# S7_Misc.net
KiCad netlist of a schematic drawn in Altium Designer
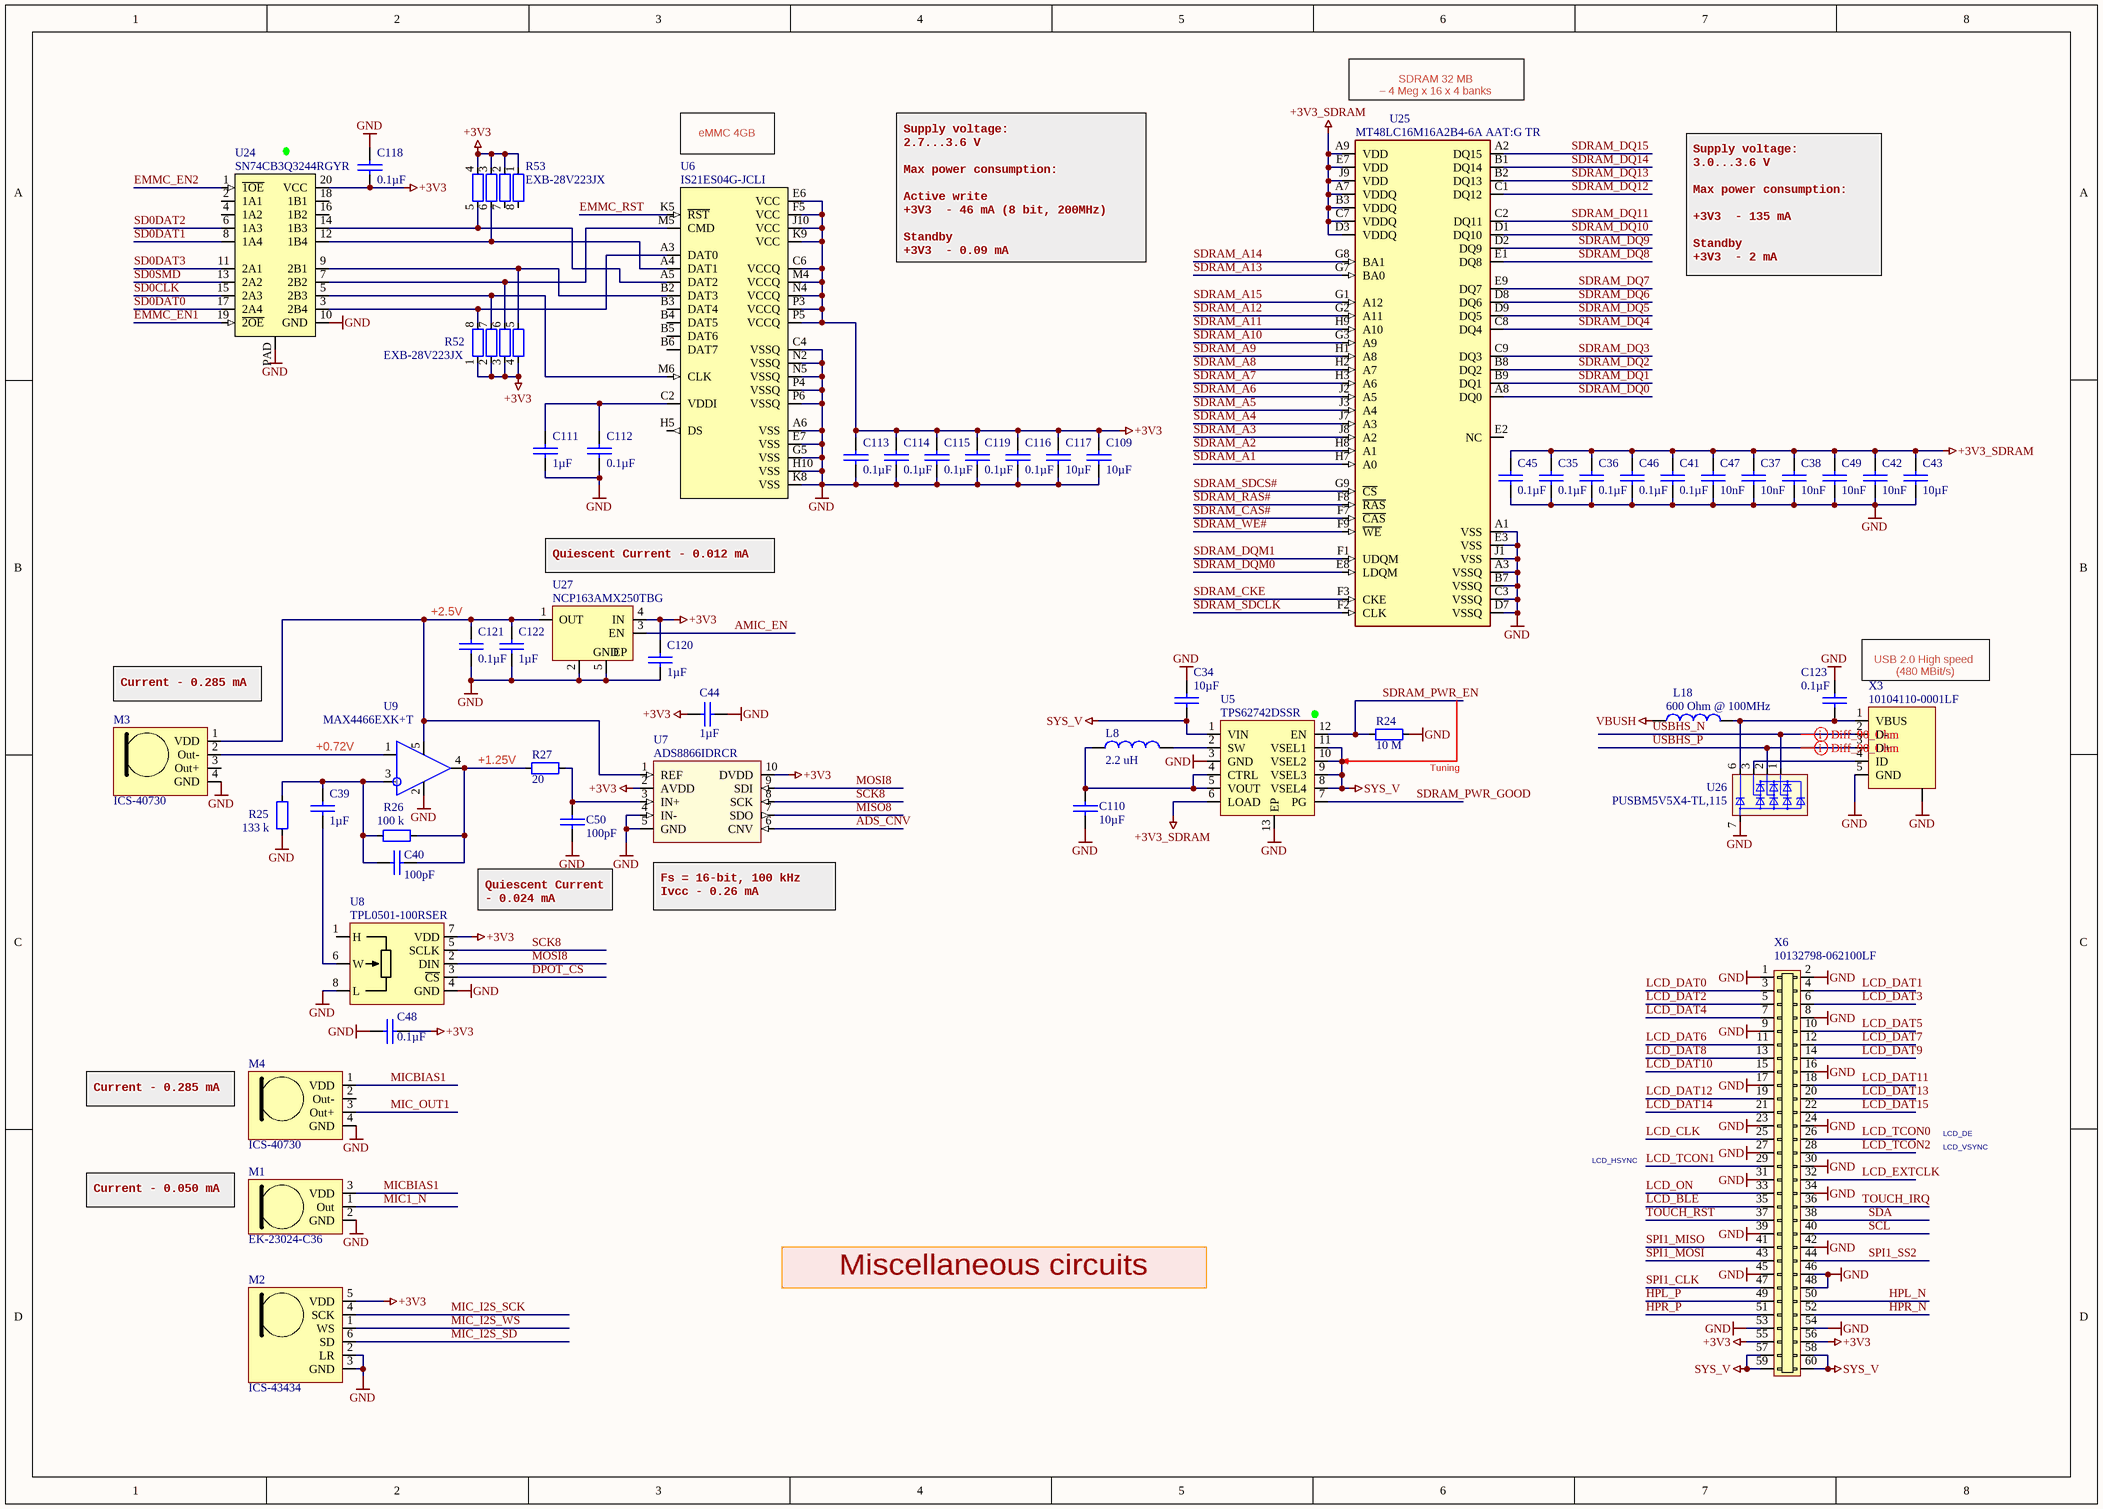
[diagram p0: S7_Misc.SchDoc]

(export (version "E")
  (design (tool "Eeschema 10.0.6"))
  (components
    (comp (ref "C34")
      (value "10µF")
      (footprint "0603 CAP")
      (description "10µF, ±10%, 16V, X5R, 0603 (1608 Metric), -55°C ~ 85°C, -, Automotive")
      (fields
        (field (name "PART NUMBER") "GRT188R61C106KE13D")
        (field (name "MANUFACTURER") "Murata Electronics North America")
      )
      (libsource (lib "ea_PassivComps") (part "Capacitor"))
    )
    (comp (ref "C35")
      (value "0.1µF")
      (footprint "0402 CAP")
      (description "0.1µF, ±10%, 50V, X7R, 0402 (1005 Metric), -55°C ~ 125°C, -, General Purpose")
      (fields
        (field (name "PART NUMBER") "0402B104K500CT")
        (field (name "MANUFACTURER") "Walsin Technology Corporation")
      )
      (libsource (lib "ea_PassivComps") (part "Capacitor"))
    )
    (comp (ref "C36")
      (value "0.1µF")
      (footprint "0402 CAP")
      (description "0.1µF, ±10%, 50V, X7R, 0402 (1005 Metric), -55°C ~ 125°C, -, General Purpose")
      (fields
        (field (name "PART NUMBER") "0402B104K500CT")
        (field (name "MANUFACTURER") "Walsin Technology Corporation")
      )
      (libsource (lib "ea_PassivComps") (part "Capacitor"))
    )
    (comp (ref "C37")
      (value "10nF")
      (footprint "0402 CAP")
      (description "10000pF, ±10%, 50V, X7R, 0402 (1005 Metric), -55°C ~ 125°C, -, General Purpose")
      (fields
        (field (name "PART NUMBER") "CL05B103KB5NNNC")
        (field (name "MANUFACTURER") "Samsung Electro-Mechanics")
      )
      (libsource (lib "ea_PassivComps") (part "Capacitor"))
    )
    (comp (ref "C38")
      (value "10nF")
      (footprint "0402 CAP")
      (description "10000pF, ±10%, 50V, X7R, 0402 (1005 Metric), -55°C ~ 125°C, -, General Purpose")
      (fields
        (field (name "PART NUMBER") "CL05B103KB5NNNC")
        (field (name "MANUFACTURER") "Samsung Electro-Mechanics")
      )
      (libsource (lib "ea_PassivComps") (part "Capacitor"))
    )
    (comp (ref "C39")
      (value "1µF")
      (footprint "0402 CAP")
      (description "1µF, ±20%, 25V, X5R, 0402 (1005 Metric), -55°C ~ 85°C, -, General Purpose")
      (fields (field (name "PART NUMBER") "TMK105BJ105MV-F") (field (name "MANUFACTURER") "Taiyo Yuden"))
      (libsource (lib "ea_PassivComps") (part "Capacitor"))
    )
    (comp (ref "C40")
      (value "100pF")
      (footprint "0402 CAP")
      (description "100pF, ±5%, 50V, C0G, NP0, 0402 (1005 Metric), -55°C ~ 125°C, -, Automotive")
      (fields (field (name "PART NUMBER") "AC0402JRNPO9BN101") (field (name "MANUFACTURER") "Yageo"))
      (libsource (lib "ea_PassivComps") (part "Capacitor"))
    )
    (comp (ref "C41")
      (value "0.1µF")
      (footprint "0402 CAP")
      (description "0.1µF, ±10%, 50V, X7R, 0402 (1005 Metric), -55°C ~ 125°C, -, General Purpose")
      (fields
        (field (name "PART NUMBER") "0402B104K500CT")
        (field (name "MANUFACTURER") "Walsin Technology Corporation")
      )
      (libsource (lib "ea_PassivComps") (part "Capacitor"))
    )
    (comp (ref "C42")
      (value "10nF")
      (footprint "0402 CAP")
      (description "10000pF, ±10%, 50V, X7R, 0402 (1005 Metric), -55°C ~ 125°C, -, General Purpose")
      (fields
        (field (name "PART NUMBER") "CL05B103KB5NNNC")
        (field (name "MANUFACTURER") "Samsung Electro-Mechanics")
      )
      (libsource (lib "ea_PassivComps") (part "Capacitor"))
    )
    (comp (ref "C43")
      (value "10µF")
      (footprint "0603 CAP")
      (description "10µF, ±10%, 16V, X5R, 0603 (1608 Metric), -55°C ~ 85°C, -, Automotive")
      (fields
        (field (name "PART NUMBER") "GRT188R61C106KE13D")
        (field (name "MANUFACTURER") "Murata Electronics North America")
      )
      (libsource (lib "ea_PassivComps") (part "Capacitor"))
    )
    (comp (ref "C44")
      (value "1µF")
      (footprint "0402 CAP")
      (description "1µF, ±20%, 25V, X5R, 0402 (1005 Metric), -55°C ~ 85°C, -, General Purpose")
      (fields (field (name "PART NUMBER") "TMK105BJ105MV-F") (field (name "MANUFACTURER") "Taiyo Yuden"))
      (libsource (lib "ea_PassivComps") (part "Capacitor"))
    )
    (comp (ref "C45")
      (value "0.1µF")
      (footprint "0402 CAP")
      (description "0.1µF, ±10%, 50V, X7R, 0402 (1005 Metric), -55°C ~ 125°C, -, General Purpose")
      (fields
        (field (name "PART NUMBER") "0402B104K500CT")
        (field (name "MANUFACTURER") "Walsin Technology Corporation")
      )
      (libsource (lib "ea_PassivComps") (part "Capacitor"))
    )
    (comp (ref "C46")
      (value "0.1µF")
      (footprint "0402 CAP")
      (description "0.1µF, ±10%, 50V, X7R, 0402 (1005 Metric), -55°C ~ 125°C, -, General Purpose")
      (fields
        (field (name "PART NUMBER") "0402B104K500CT")
        (field (name "MANUFACTURER") "Walsin Technology Corporation")
      )
      (libsource (lib "ea_PassivComps") (part "Capacitor"))
    )
    (comp (ref "C47")
      (value "10nF")
      (footprint "0402 CAP")
      (description "10000pF, ±10%, 50V, X7R, 0402 (1005 Metric), -55°C ~ 125°C, -, General Purpose")
      (fields
        (field (name "PART NUMBER") "CL05B103KB5NNNC")
        (field (name "MANUFACTURER") "Samsung Electro-Mechanics")
      )
      (libsource (lib "ea_PassivComps") (part "Capacitor"))
    )
    (comp (ref "C48")
      (value "0.1µF")
      (footprint "0402 CAP")
      (description "0.1µF, ±10%, 50V, X7R, 0402 (1005 Metric), -55°C ~ 125°C, -, General Purpose")
      (fields
        (field (name "PART NUMBER") "0402B104K500CT")
        (field (name "MANUFACTURER") "Walsin Technology Corporation")
      )
      (libsource (lib "ea_PassivComps") (part "Capacitor"))
    )
    (comp (ref "C49")
      (value "10nF")
      (footprint "0402 CAP")
      (description "10000pF, ±10%, 50V, X7R, 0402 (1005 Metric), -55°C ~ 125°C, -, General Purpose")
      (fields
        (field (name "PART NUMBER") "CL05B103KB5NNNC")
        (field (name "MANUFACTURER") "Samsung Electro-Mechanics")
      )
      (libsource (lib "ea_PassivComps") (part "Capacitor"))
    )
    (comp (ref "C50")
      (value "100pF")
      (footprint "0402 CAP")
      (description "100pF, ±5%, 50V, C0G, NP0, 0402 (1005 Metric), -55°C ~ 125°C, -, Automotive")
      (fields (field (name "PART NUMBER") "AC0402JRNPO9BN101") (field (name "MANUFACTURER") "Yageo"))
      (libsource (lib "ea_PassivComps") (part "Capacitor"))
    )
    (comp (ref "C109")
      (value "10µF")
      (footprint "0603 CAP")
      (description "10µF, ±10%, 16V, X5R, 0603 (1608 Metric), -55°C ~ 85°C, -, Automotive")
      (fields
        (field (name "PART NUMBER") "GRT188R61C106KE13D")
        (field (name "MANUFACTURER") "Murata Electronics North America")
      )
      (libsource (lib "ea_PassivComps") (part "Capacitor"))
    )
    (comp (ref "C110")
      (value "10µF")
      (footprint "0603 CAP")
      (description "10µF, ±10%, 16V, X5R, 0603 (1608 Metric), -55°C ~ 85°C, -, Automotive")
      (fields
        (field (name "PART NUMBER") "GRT188R61C106KE13D")
        (field (name "MANUFACTURER") "Murata Electronics North America")
      )
      (libsource (lib "ea_PassivComps") (part "Capacitor"))
    )
    (comp (ref "C111")
      (value "1µF")
      (footprint "0402 CAP")
      (description "1µF, ±20%, 25V, X5R, 0402 (1005 Metric), -55°C ~ 85°C, -, General Purpose")
      (fields (field (name "PART NUMBER") "TMK105BJ105MV-F") (field (name "MANUFACTURER") "Taiyo Yuden"))
      (libsource (lib "ea_PassivComps") (part "Capacitor"))
    )
    (comp (ref "C112")
      (value "0.1µF")
      (footprint "0402 CAP")
      (description "0.1µF, ±10%, 50V, X7R, 0402 (1005 Metric), -55°C ~ 125°C, -, General Purpose")
      (fields
        (field (name "PART NUMBER") "0402B104K500CT")
        (field (name "MANUFACTURER") "Walsin Technology Corporation")
      )
      (libsource (lib "ea_PassivComps") (part "Capacitor"))
    )
    (comp (ref "C113")
      (value "0.1µF")
      (footprint "0402 CAP")
      (description "0.1µF, ±10%, 50V, X7R, 0402 (1005 Metric), -55°C ~ 125°C, -, General Purpose")
      (fields
        (field (name "PART NUMBER") "0402B104K500CT")
        (field (name "MANUFACTURER") "Walsin Technology Corporation")
      )
      (libsource (lib "ea_PassivComps") (part "Capacitor"))
    )
    (comp (ref "C114")
      (value "0.1µF")
      (footprint "0402 CAP")
      (description "0.1µF, ±10%, 50V, X7R, 0402 (1005 Metric), -55°C ~ 125°C, -, General Purpose")
      (fields
        (field (name "PART NUMBER") "0402B104K500CT")
        (field (name "MANUFACTURER") "Walsin Technology Corporation")
      )
      (libsource (lib "ea_PassivComps") (part "Capacitor"))
    )
    (comp (ref "C115")
      (value "0.1µF")
      (footprint "0402 CAP")
      (description "0.1µF, ±10%, 50V, X7R, 0402 (1005 Metric), -55°C ~ 125°C, -, General Purpose")
      (fields
        (field (name "PART NUMBER") "0402B104K500CT")
        (field (name "MANUFACTURER") "Walsin Technology Corporation")
      )
      (libsource (lib "ea_PassivComps") (part "Capacitor"))
    )
    (comp (ref "C116")
      (value "0.1µF")
      (footprint "0402 CAP")
      (description "0.1µF, ±10%, 50V, X7R, 0402 (1005 Metric), -55°C ~ 125°C, -, General Purpose")
      (fields
        (field (name "PART NUMBER") "0402B104K500CT")
        (field (name "MANUFACTURER") "Walsin Technology Corporation")
      )
      (libsource (lib "ea_PassivComps") (part "Capacitor"))
    )
    (comp (ref "C117")
      (value "10µF")
      (footprint "0603 CAP")
      (description "10µF, ±10%, 16V, X5R, 0603 (1608 Metric), -55°C ~ 85°C, -, Automotive")
      (fields
        (field (name "PART NUMBER") "GRT188R61C106KE13D")
        (field (name "MANUFACTURER") "Murata Electronics North America")
      )
      (libsource (lib "ea_PassivComps") (part "Capacitor"))
    )
    (comp (ref "C118")
      (value "0.1µF")
      (footprint "0402 CAP")
      (description "0.1µF, ±10%, 50V, X7R, 0402 (1005 Metric), -55°C ~ 125°C, -, General Purpose")
      (fields
        (field (name "PART NUMBER") "0402B104K500CT")
        (field (name "MANUFACTURER") "Walsin Technology Corporation")
      )
      (libsource (lib "ea_PassivComps") (part "Capacitor"))
    )
    (comp (ref "C119")
      (value "0.1µF")
      (footprint "0402 CAP")
      (description "0.1µF, ±10%, 50V, X7R, 0402 (1005 Metric), -55°C ~ 125°C, -, General Purpose")
      (fields
        (field (name "PART NUMBER") "0402B104K500CT")
        (field (name "MANUFACTURER") "Walsin Technology Corporation")
      )
      (libsource (lib "ea_PassivComps") (part "Capacitor"))
    )
    (comp (ref "C120")
      (value "1µF")
      (footprint "0402 CAP")
      (description "1µF, ±20%, 25V, X5R, 0402 (1005 Metric), -55°C ~ 85°C, -, General Purpose")
      (fields (field (name "PART NUMBER") "TMK105BJ105MV-F") (field (name "MANUFACTURER") "Taiyo Yuden"))
      (libsource (lib "ea_PassivComps") (part "Capacitor"))
    )
    (comp (ref "C121")
      (value "0.1µF")
      (footprint "0402 CAP")
      (description "0.1µF, ±10%, 50V, X7R, 0402 (1005 Metric), -55°C ~ 125°C, -, General Purpose")
      (fields
        (field (name "PART NUMBER") "0402B104K500CT")
        (field (name "MANUFACTURER") "Walsin Technology Corporation")
      )
      (libsource (lib "ea_PassivComps") (part "Capacitor"))
    )
    (comp (ref "C122")
      (value "1µF")
      (footprint "0402 CAP")
      (description "1µF, ±20%, 25V, X5R, 0402 (1005 Metric), -55°C ~ 85°C, -, General Purpose")
      (fields (field (name "PART NUMBER") "TMK105BJ105MV-F") (field (name "MANUFACTURER") "Taiyo Yuden"))
      (libsource (lib "ea_PassivComps") (part "Capacitor"))
    )
    (comp (ref "C123")
      (value "0.1µF")
      (footprint "0402 CAP")
      (description "0.1µF, ±10%, 50V, X7R, 0402 (1005 Metric), -55°C ~ 125°C, -, General Purpose")
      (fields
        (field (name "PART NUMBER") "0402B104K500CT")
        (field (name "MANUFACTURER") "Walsin Technology Corporation")
      )
      (libsource (lib "ea_PassivComps") (part "Capacitor"))
    )
    (comp (ref "L8")
      (value "2.2 uH")
      (footprint "744025002")
      (description "Inductors 2.2 uH, 1.8 A, 0.066 Ohms, ±20% -40°C ~ 125°C, 2.8 x 2.8 mm")
      (fields (field (name "MANUFACTURER") "Wurth Electronics Inc") (field (name "PARTNUM") "732-2613-1-ND"))
      (libsource (lib "ea_Inductors") (part "744025002"))
    )
    (comp (ref "L18")
      (value "600 Ohm @ 100MHz")
      (footprint "0805")
      (description "FERRITE BEAD 600 OHM, 0805, -55°C ~ 125°C")
      (fields (field (name "MANUFACTURER") "TDK Corporation") (field (name "PARTNUM") "445-2206-1-ND"))
      (libsource (lib "ea_Inductors") (part "MPZ2012S601AT000"))
    )
    (comp (ref "M1")
      (value "EK-23024-C36")
      (footprint "EK-23024-C36")
      (fields (field (name "MANUFACTURER") "Knowles") (field (name "PARTNUM") "423-1121-ND"))
      (libsource (lib "ea_Sound_devices") (part "EK-23024-C36"))
    )
    (comp (ref "M2")
      (value "ICS-43434")
      (footprint "ICS-43434")
      (fields (field (name "MANUFACTURER") "TDK InvenSense") (field (name "PARTNUM") "1428-1066-1-ND"))
      (libsource (lib "ea_Sound_devices") (part "ICS-43434"))
    )
    (comp (ref "M3")
      (value "ICS-40730")
      (footprint "ICS-40730")
      (fields (field (name "MANUFACTURER") "TDK InvenSense") (field (name "PARTNUM") "1428-1141-1-ND"))
      (libsource (lib "ea_Sound_devices") (part "ICS-40730"))
    )
    (comp (ref "M4")
      (value "ICS-40730")
      (footprint "ICS-40730")
      (fields (field (name "MANUFACTURER") "TDK InvenSense") (field (name "PARTNUM") "1428-1141-1-ND"))
      (libsource (lib "ea_Sound_devices") (part "ICS-40730"))
    )
    (comp (ref "R24")
      (value "10 M")
      (footprint "0402")
      (description "10 MOhms, ±1%, 0.063W, 1/16W, Thick Film, ±100ppm/°C, 0402 (1005 Metric), -55°C ~ 155°C, -")
      (fields (field (name "MANUFACTURER") "Vishay Dale") (field (name "TOLERANCE") "±1%"))
      (libsource (lib "") (part "Resistor_1"))
    )
    (comp (ref "R25")
      (value "133 k")
      (footprint "0402")
      (fields
        (field (name "MANUFACTURER") "Stackpole Electronics Inc")
        (field (name "TOLERANCE") "±1%")
        (field (name "VOLTAGE") "75V")
      )
      (libsource (lib "ea_PassivComps") (part "Resistor"))
    )
    (comp (ref "R26")
      (value "100 k")
      (footprint "0402")
      (fields
        (field (name "MANUFACTURER") "Stackpole Electronics Inc")
        (field (name "TOLERANCE") "±1%")
        (field (name "VOLTAGE") "75V")
      )
      (libsource (lib "") (part "Resistor_1"))
    )
    (comp (ref "R27")
      (value "20")
      (footprint "0402")
      (fields
        (field (name "MANUFACTURER") "Stackpole Electronics Inc")
        (field (name "TOLERANCE") "±1%")
        (field (name "VOLTAGE") "75V")
      )
      (libsource (lib "") (part "Resistor_1"))
    )
    (comp (ref "R52")
      (value "EXB-28V223JX")
      (footprint "EXB28V 2x1 mm")
      (description "22k Ohm ±5%,  4 Resistor, -55°C ~ 125°C,(2.00mm x 1.00mm)")
      (fields (field (name "MANUFACTURER") "Panasonic Electronic Components") (field (name "TOLERANCE") "5%"))
      (libsource (lib "") (part "EXB-28V223JX_1"))
    )
    (comp (ref "R53")
      (value "EXB-28V223JX")
      (footprint "EXB28V 2x1 mm")
      (description "22k Ohm ±5%,  4 Resistor, -55°C ~ 125°C,(2.00mm x 1.00mm)")
      (fields (field (name "MANUFACTURER") "Panasonic Electronic Components") (field (name "TOLERANCE") "5%"))
      (libsource (lib "ea_Resistors") (part "EXB-28V223JX"))
    )
    (comp (ref "U5")
      (value "TPS62742DSSR")
      (footprint "12-WSON")
      (description "DCDC 1.8-3.3V, 400mA , Iq=360nA, -40°C ~ 85°C, 12-WSON (3x2)")
      (fields (field (name "MANUFACTURER") "Texas Instruments") (field (name "PARTNUM") "296-40852-1-ND"))
      (libsource (lib "ea_IC_Power_Reg_Ref_Sw") (part "TPS62742DSSR"))
    )
    (comp (ref "U6")
      (value "IS21ES04G-JCLI")
      (footprint "MICRON_WFBGA153")
      (description "4GByte eMMC, 200MHz, 2.7V ~ 3.6V, 153-VFBGA (11.5x13),  -40°C ~ 85°C")
      (fields
        (field (name "MANUFACTURER") "Integrated Silicon Solution Inc")
        (field (name "DISPLAY NAME") "IS21ES04G-JCLI")
      )
      (libsource (lib "ea_IC_NOR_NAND_FLASH") (part "IS21ES04G-JCLI"))
    )
    (comp (ref "U7")
      (value "ADS8866IDRCR")
      (footprint "TI S-PVSON-N10")
      (description "16-bit ADC, 100k, Pseudo-Differential, Single Ended, 2.7..3.6V,  -40°C...85°C, 10-VSON")
      (fields (field (name "MANUFACTURER") "Texas Instruments") (field (name "PARTNUM") "296-39886-1-ND"))
      (libsource (lib "ea_IC_ADC") (part "ADS8866IDRCR"))
    )
    (comp (ref "U8")
      (value "TPL0501-100RSER")
      (footprint "UQFN-8")
      (description "Digital Potentiometer 100k Ohm 1 Circuit 256 Taps SPI Interface, -40°C ~ 125°C,  8-UQFN (1.5x1.5)")
      (fields (field (name "MANUFACTURER") "Texas Instruments") (field (name "PARTNUM") "296-29585-1-ND"))
      (libsource (lib "ea_IC_Digital_Potentiometers") (part "TPL0501-100RSER"))
    )
    (comp (ref "U9")
      (value "MAX4466EXK+T")
      (footprint "SOT-353 ON Semi")
      (description "OpAmp, Class AB,  2.4V ~ 5.5V, -40°C ~ 85°C, SC-70-5")
      (fields (field (name "MANUFACTURER") "Maxim Integrated") (field (name "PARTNUM") "MAX4466EXK+CT-ND"))
      (libsource (lib "ea_IC_OPAmps_AnComparators") (part "MAX4466EXK+T"))
    )
    (comp (ref "U24")
      (value "SN74CB3Q3244RGYR")
      (footprint "TI_PVQFN-N20")
      (description "Bus Switch 4 x 1:1, 2.3V ~ 3.6V,  -40°C ~ 85°C, 20-VQFN (3.5x4.5)")
      (fields (field (name "MANUFACTURER") "Texas Instruments") (field (name "PARTNUM") "296-19127-1-ND"))
      (libsource (lib "ea_IC_registers_buffers") (part "SN74CB3Q3244RGYR"))
    )
    (comp (ref "U25")
      (value "MT48LC16M16A2B4-6A AAT:G TR")
      (footprint "MICRON_VFBGA54")
      (description "Micron SDRAM 256M-Bit 16Mx16, 3.3V, 167MHz, 5.4ns, -40°C ~ 105°C, 54-VFBGA (8x8)")
      (fields (field (name "MANUFACTURER") "Micron Technology Inc.") (field (name "PARTNUM") "557-1932-1-ND"))
      (libsource (lib "ea_IC_RAM") (part "MT48LC16M16A2B4-6A AAT{colon}G TR"))
    )
    (comp (ref "U26")
      (value "PUSBM5V5X4-TL,115")
      (footprint "DFN1616-6")
      (description "TVS DIODE 5.5VWM 12VC 6HXSON")
      (fields (field (name "MANUFACTURER") "NXP Semiconductors") (field (name "PARTNUM") "568-10921-1-ND"))
      (libsource (lib "ea_TVS_protection") (part "PUSBM5V5X4-TL,115"))
    )
    (comp (ref "U27")
      (value "NCP163AMX250TBG")
      (footprint "4-XDFN")
      (description "LDO 2.5V, 250 mA, Vin < 5.5V, Iq < 20uA, -40..+125 C,  4-XDFN (1x1)")
      (fields
        (field (name "MANUFACTURER") "ON Semiconductor")
        (field (name "PARTNUM") "NCP163AMX250TBGOSCT-ND")
      )
      (libsource (lib "ea_IC_Power_Reg_Ref_Sw") (part "NCP163AMX250TBG"))
    )
    (comp (ref "X3")
      (value "10104110-0001LF")
      (footprint "FCI micro USB B receptacle SMD")
      (description "USB - micro B USB 2.0 Receptacle Connector 5 Position Surface Mount, Right Angle")
      (fields (field (name "MANUFACTURER") "Amphenol FCI") (field (name "PARTNUM") "609-4052-1-ND"))
      (libsource (lib "ea_Connectors_USB") (part "10104110-0001LF"))
    )
    (comp (ref "X6")
      (value "10132798-062100LF")
      (footprint "10132798-062100LF")
      (fields (field (name "MANUFACTURER") "Amphenol ICC (FCI)") (field (name "PARTNUM") "609-5230-1-ND"))
      (libsource (lib "ea_Connectors_0.5_mm_pitch") (part "10132798-062100LF"))
    )
  )
  (nets
    (net (code "1") (name "+3V3") (class "Default")
      (node (ref "C109") (pin "1") (pinfunction "1_1") (pintype "passive"))
      (node (ref "C113") (pin "1") (pinfunction "1_1") (pintype "passive"))
      (node (ref "C114") (pin "1") (pinfunction "1_1") (pintype "passive"))
      (node (ref "C115") (pin "1") (pinfunction "1_1") (pintype "passive"))
      (node (ref "C116") (pin "1") (pinfunction "1_1") (pintype "passive"))
      (node (ref "C117") (pin "1") (pinfunction "1_1") (pintype "passive"))
      (node (ref "C118") (pin "2") (pinfunction "2_2") (pintype "passive"))
      (node (ref "C119") (pin "1") (pinfunction "1_1") (pintype "passive"))
      (node (ref "C120") (pin "1") (pinfunction "1_1") (pintype "passive"))
      (node (ref "C44") (pin "1") (pinfunction "1_1") (pintype "passive"))
      (node (ref "C48") (pin "2") (pinfunction "2_2") (pintype "passive"))
      (node (ref "M2") (pin "5") (pinfunction "VDD_5") (pintype "passive"))
      (node (ref "R52") (pin "1") (pinfunction "1_1") (pintype "passive"))
      (node (ref "R52") (pin "2") (pinfunction "2_2") (pintype "passive"))
      (node (ref "R52") (pin "3") (pinfunction "3_3") (pintype "passive"))
      (node (ref "R52") (pin "4") (pinfunction "4_4") (pintype "passive"))
      (node (ref "R53") (pin "1") (pinfunction "1_1") (pintype "passive"))
      (node (ref "R53") (pin "2") (pinfunction "2_2") (pintype "passive"))
      (node (ref "R53") (pin "3") (pinfunction "3_3") (pintype "passive"))
      (node (ref "R53") (pin "4") (pinfunction "4_4") (pintype "passive"))
      (node (ref "U24") (pin "20") (pinfunction "VCC_20") (pintype "power_in"))
      (node (ref "U27") (pin "4") (pinfunction "IN_4") (pintype "power_in"))
      (node (ref "U6") (pin "C6") (pinfunction "VCCQ_C6") (pintype "power_in"))
      (node (ref "U6") (pin "E6") (pinfunction "VCC_E6") (pintype "power_in"))
      (node (ref "U6") (pin "F5") (pinfunction "VCC_F5") (pintype "power_in"))
      (node (ref "U6") (pin "J10") (pinfunction "VCC_J10") (pintype "power_in"))
      (node (ref "U6") (pin "K9") (pinfunction "VCC_K9") (pintype "power_in"))
      (node (ref "U6") (pin "M4") (pinfunction "VCCQ_M4") (pintype "power_in"))
      (node (ref "U6") (pin "N4") (pinfunction "VCCQ_N4") (pintype "power_in"))
      (node (ref "U6") (pin "P3") (pinfunction "VCCQ_P3") (pintype "power_in"))
      (node (ref "U6") (pin "P5") (pinfunction "VCCQ_P5") (pintype "power_in"))
      (node (ref "U7") (pin "10") (pinfunction "DVDD_10") (pintype "power_in"))
      (node (ref "U7") (pin "2") (pinfunction "AVDD_2") (pintype "power_in"))
      (node (ref "U8") (pin "7") (pinfunction "VDD_7") (pintype "passive"))
      (node (ref "X6") (pin "55") (pinfunction "28_55") (pintype "passive"))
      (node (ref "X6") (pin "56") (pinfunction "29_56") (pintype "passive"))
    )
    (net (code "2") (name "+3V3_SDRAM") (class "Default")
      (node (ref "C35") (pin "1") (pinfunction "1_1") (pintype "passive"))
      (node (ref "C36") (pin "1") (pinfunction "1_1") (pintype "passive"))
      (node (ref "C37") (pin "1") (pinfunction "1_1") (pintype "passive"))
      (node (ref "C38") (pin "1") (pinfunction "1_1") (pintype "passive"))
      (node (ref "C41") (pin "1") (pinfunction "1_1") (pintype "passive"))
      (node (ref "C42") (pin "1") (pinfunction "1_1") (pintype "passive"))
      (node (ref "C43") (pin "1") (pinfunction "1_1") (pintype "passive"))
      (node (ref "C45") (pin "1") (pinfunction "1_1") (pintype "passive"))
      (node (ref "C46") (pin "1") (pinfunction "1_1") (pintype "passive"))
      (node (ref "C47") (pin "1") (pinfunction "1_1") (pintype "passive"))
      (node (ref "C49") (pin "1") (pinfunction "1_1") (pintype "passive"))
      (node (ref "U25") (pin "A7") (pinfunction "VDDQ_A7") (pintype "power_in"))
      (node (ref "U25") (pin "A9") (pinfunction "VDD_A9") (pintype "power_in"))
      (node (ref "U25") (pin "B3") (pinfunction "VDDQ_B3") (pintype "power_in"))
      (node (ref "U25") (pin "C7") (pinfunction "VDDQ_C7") (pintype "power_in"))
      (node (ref "U25") (pin "D3") (pinfunction "VDDQ_D3") (pintype "power_in"))
      (node (ref "U25") (pin "E7") (pinfunction "VDD_E7") (pintype "power_in"))
      (node (ref "U25") (pin "J9") (pinfunction "VDD_J9") (pintype "power_in"))
      (node (ref "U5") (pin "6") (pinfunction "LOAD_6") (pintype "passive"))
    )
    (net (code "3") (name "/ADS_CNV") (class "Default")
      (node (ref "U7") (pin "6") (pinfunction "CNV_6") (pintype "input"))
    )
    (net (code "4") (name "/AMIC_EN") (class "Default")
      (node (ref "U27") (pin "3") (pinfunction "EN_3") (pintype "power_in"))
    )
    (net (code "5") (name "/DPOT_CS") (class "Default")
      (node (ref "U8") (pin "3") (pinfunction "~{CS}_3") (pintype "passive"))
    )
    (net (code "6") (name "/EMMC_EN1") (class "Default")
      (node (ref "U24") (pin "19") (pinfunction "~{2OE}_19") (pintype "input"))
    )
    (net (code "7") (name "/EMMC_EN2") (class "Default")
      (node (ref "U24") (pin "1") (pinfunction "~{1OE}_1") (pintype "input"))
    )
    (net (code "8") (name "/EMMC_RST") (class "Default")
      (node (ref "U6") (pin "K5") (pinfunction "~{RST}_K5") (pintype "input"))
    )
    (net (code "9") (name "/HPL_N") (class "Default")
      (node (ref "X6") (pin "50") (pinfunction "26_50") (pintype "passive"))
    )
    (net (code "10") (name "/HPL_P") (class "Default")
      (node (ref "X6") (pin "49") (pinfunction "25_49") (pintype "passive"))
    )
    (net (code "11") (name "/HPR_N") (class "Default")
      (node (ref "X6") (pin "52") (pinfunction "27_52") (pintype "passive"))
    )
    (net (code "12") (name "/HPR_P") (class "Default")
      (node (ref "X6") (pin "51") (pinfunction "26_51") (pintype "passive"))
    )
    (net (code "13") (name "/LCD_BLE") (class "Default")
      (node (ref "X6") (pin "35") (pinfunction "18_35") (pintype "passive"))
    )
    (net (code "14") (name "/LCD_CLK") (class "Default")
      (node (ref "X6") (pin "25") (pinfunction "13_25") (pintype "passive"))
    )
    (net (code "15") (name "/LCD_DAT0") (class "Default")
      (node (ref "X6") (pin "3") (pinfunction "2_3") (pintype "passive"))
    )
    (net (code "16") (name "/LCD_DAT1") (class "Default")
      (node (ref "X6") (pin "4") (pinfunction "3_4") (pintype "passive"))
    )
    (net (code "17") (name "/LCD_DAT2") (class "Default")
      (node (ref "X6") (pin "5") (pinfunction "3_5") (pintype "passive"))
    )
    (net (code "18") (name "/LCD_DAT3") (class "Default")
      (node (ref "X6") (pin "6") (pinfunction "4_6") (pintype "passive"))
    )
    (net (code "19") (name "/LCD_DAT4") (class "Default")
      (node (ref "X6") (pin "7") (pinfunction "4_7") (pintype "passive"))
    )
    (net (code "20") (name "/LCD_DAT5") (class "Default")
      (node (ref "X6") (pin "10") (pinfunction "6_10") (pintype "passive"))
    )
    (net (code "21") (name "/LCD_DAT6") (class "Default")
      (node (ref "X6") (pin "11") (pinfunction "6_11") (pintype "passive"))
    )
    (net (code "22") (name "/LCD_DAT7") (class "Default")
      (node (ref "X6") (pin "12") (pinfunction "7_12") (pintype "passive"))
    )
    (net (code "23") (name "/LCD_DAT8") (class "Default")
      (node (ref "X6") (pin "13") (pinfunction "7_13") (pintype "passive"))
    )
    (net (code "24") (name "/LCD_DAT9") (class "Default")
      (node (ref "X6") (pin "14") (pinfunction "8_14") (pintype "passive"))
    )
    (net (code "25") (name "/LCD_DAT10") (class "Default")
      (node (ref "X6") (pin "15") (pinfunction "8_15") (pintype "passive"))
    )
    (net (code "26") (name "/LCD_DAT11") (class "Default")
      (node (ref "X6") (pin "18") (pinfunction "10_18") (pintype "passive"))
    )
    (net (code "27") (name "/LCD_DAT12") (class "Default")
      (node (ref "X6") (pin "19") (pinfunction "10_19") (pintype "passive"))
    )
    (net (code "28") (name "/LCD_DAT13") (class "Default")
      (node (ref "X6") (pin "20") (pinfunction "11_20") (pintype "passive"))
    )
    (net (code "29") (name "/LCD_DAT14") (class "Default")
      (node (ref "X6") (pin "21") (pinfunction "11_21") (pintype "passive"))
    )
    (net (code "30") (name "/LCD_DAT15") (class "Default")
      (node (ref "X6") (pin "22") (pinfunction "12_22") (pintype "passive"))
    )
    (net (code "31") (name "/LCD_EXTCLK") (class "Default")
      (node (ref "X6") (pin "32") (pinfunction "17_32") (pintype "passive"))
    )
    (net (code "32") (name "/LCD_ON") (class "Default")
      (node (ref "X6") (pin "33") (pinfunction "17_33") (pintype "passive"))
    )
    (net (code "33") (name "/LCD_TCON0") (class "Default")
      (node (ref "X6") (pin "26") (pinfunction "14_26") (pintype "passive"))
    )
    (net (code "34") (name "/LCD_TCON1") (class "Default")
      (node (ref "X6") (pin "29") (pinfunction "15_29") (pintype "passive"))
    )
    (net (code "35") (name "/LCD_TCON2") (class "Default")
      (node (ref "X6") (pin "28") (pinfunction "15_28") (pintype "passive"))
    )
    (net (code "36") (name "/MIC1_N") (class "Default")
      (node (ref "M1") (pin "1") (pinfunction "Out_1") (pintype "passive"))
    )
    (net (code "37") (name "/MICBIAS1") (class "Default")
      (node (ref "M1") (pin "3") (pinfunction "VDD_3") (pintype "passive"))
      (node (ref "M4") (pin "1") (pinfunction "VDD_1") (pintype "passive"))
    )
    (net (code "38") (name "/MIC_I2S_SCK") (class "Default")
      (node (ref "M2") (pin "4") (pinfunction "SCK_4") (pintype "passive"))
    )
    (net (code "39") (name "/MIC_I2S_SD") (class "Default")
      (node (ref "M2") (pin "6") (pinfunction "SD_6") (pintype "passive"))
    )
    (net (code "40") (name "/MIC_I2S_WS") (class "Default")
      (node (ref "M2") (pin "1") (pinfunction "WS_1") (pintype "passive"))
    )
    (net (code "41") (name "/MIC_OUT1") (class "Default")
      (node (ref "M4") (pin "3") (pinfunction "Out+_3") (pintype "passive"))
    )
    (net (code "42") (name "/MISO8") (class "Default")
      (node (ref "U7") (pin "7") (pinfunction "SDO_7") (pintype "output"))
    )
    (net (code "43") (name "/MOSI8") (class "Default")
      (node (ref "U7") (pin "9") (pinfunction "SDI_9") (pintype "input"))
      (node (ref "U8") (pin "2") (pinfunction "DIN_2") (pintype "passive"))
    )
    (net (code "44") (name "/SCK8") (class "Default")
      (node (ref "U7") (pin "8") (pinfunction "SCK_8") (pintype "input"))
      (node (ref "U8") (pin "5") (pinfunction "SCLK_5") (pintype "passive"))
    )
    (net (code "45") (name "/SCL") (class "Default")
      (node (ref "X6") (pin "40") (pinfunction "21_40") (pintype "passive"))
    )
    (net (code "46") (name "/SD0CLK") (class "Default")
      (node (ref "U24") (pin "15") (pinfunction "2A3_15") (pintype "bidirectional"))
    )
    (net (code "47") (name "/SD0DAT0") (class "Default")
      (node (ref "U24") (pin "17") (pinfunction "2A4_17") (pintype "bidirectional"))
    )
    (net (code "48") (name "/SD0DAT1") (class "Default")
      (node (ref "U24") (pin "8") (pinfunction "1A4_8") (pintype "bidirectional"))
    )
    (net (code "49") (name "/SD0DAT2") (class "Default")
      (node (ref "U24") (pin "6") (pinfunction "1A3_6") (pintype "bidirectional"))
    )
    (net (code "50") (name "/SD0DAT3") (class "Default")
      (node (ref "U24") (pin "11") (pinfunction "2A1_11") (pintype "bidirectional"))
    )
    (net (code "51") (name "/SD0SMD") (class "Default")
      (node (ref "U24") (pin "13") (pinfunction "2A2_13") (pintype "bidirectional"))
    )
    (net (code "52") (name "/SDA") (class "Default")
      (node (ref "X6") (pin "38") (pinfunction "20_38") (pintype "passive"))
    )
    (net (code "53") (name "/SDRAM_A1") (class "Default")
      (node (ref "U25") (pin "H7") (pinfunction "A0_H7") (pintype "input"))
    )
    (net (code "54") (name "/SDRAM_A2") (class "Default")
      (node (ref "U25") (pin "H8") (pinfunction "A1_H8") (pintype "input"))
    )
    (net (code "55") (name "/SDRAM_A3") (class "Default")
      (node (ref "U25") (pin "J8") (pinfunction "A2_J8") (pintype "input"))
    )
    (net (code "56") (name "/SDRAM_A4") (class "Default")
      (node (ref "U25") (pin "J7") (pinfunction "A3_J7") (pintype "input"))
    )
    (net (code "57") (name "/SDRAM_A5") (class "Default")
      (node (ref "U25") (pin "J3") (pinfunction "A4_J3") (pintype "input"))
    )
    (net (code "58") (name "/SDRAM_A6") (class "Default")
      (node (ref "U25") (pin "J2") (pinfunction "A5_J2") (pintype "input"))
    )
    (net (code "59") (name "/SDRAM_A7") (class "Default")
      (node (ref "U25") (pin "H3") (pinfunction "A6_H3") (pintype "input"))
    )
    (net (code "60") (name "/SDRAM_A8") (class "Default")
      (node (ref "U25") (pin "H2") (pinfunction "A7_H2") (pintype "input"))
    )
    (net (code "61") (name "/SDRAM_A9") (class "Default")
      (node (ref "U25") (pin "H1") (pinfunction "A8_H1") (pintype "input"))
    )
    (net (code "62") (name "/SDRAM_A10") (class "Default")
      (node (ref "U25") (pin "G3") (pinfunction "A9_G3") (pintype "input"))
    )
    (net (code "63") (name "/SDRAM_A11") (class "Default")
      (node (ref "U25") (pin "H9") (pinfunction "A10_H9") (pintype "input"))
    )
    (net (code "64") (name "/SDRAM_A12") (class "Default")
      (node (ref "U25") (pin "G2") (pinfunction "A11_G2") (pintype "input"))
    )
    (net (code "65") (name "/SDRAM_A13") (class "Default")
      (node (ref "U25") (pin "G7") (pinfunction "BA0_G7") (pintype "input"))
    )
    (net (code "66") (name "/SDRAM_A14") (class "Default")
      (node (ref "U25") (pin "G8") (pinfunction "BA1_G8") (pintype "input"))
    )
    (net (code "67") (name "/SDRAM_A15") (class "Default")
      (node (ref "U25") (pin "G1") (pinfunction "A12_G1") (pintype "input"))
    )
    (net (code "68") (name "/SDRAM_CAS#") (class "Default")
      (node (ref "U25") (pin "F7") (pinfunction "~{CAS}_F7") (pintype "input"))
    )
    (net (code "69") (name "/SDRAM_CKE") (class "Default")
      (node (ref "U25") (pin "F3") (pinfunction "CKE_F3") (pintype "input"))
    )
    (net (code "70") (name "/SDRAM_DQ0") (class "Default")
      (node (ref "U25") (pin "A8") (pinfunction "DQ0_A8") (pintype "bidirectional"))
    )
    (net (code "71") (name "/SDRAM_DQ1") (class "Default")
      (node (ref "U25") (pin "B9") (pinfunction "DQ1_B9") (pintype "bidirectional"))
    )
    (net (code "72") (name "/SDRAM_DQ2") (class "Default")
      (node (ref "U25") (pin "B8") (pinfunction "DQ2_B8") (pintype "bidirectional"))
    )
    (net (code "73") (name "/SDRAM_DQ3") (class "Default")
      (node (ref "U25") (pin "C9") (pinfunction "DQ3_C9") (pintype "bidirectional"))
    )
    (net (code "74") (name "/SDRAM_DQ4") (class "Default")
      (node (ref "U25") (pin "C8") (pinfunction "DQ4_C8") (pintype "bidirectional"))
    )
    (net (code "75") (name "/SDRAM_DQ5") (class "Default")
      (node (ref "U25") (pin "D9") (pinfunction "DQ5_D9") (pintype "bidirectional"))
    )
    (net (code "76") (name "/SDRAM_DQ6") (class "Default")
      (node (ref "U25") (pin "D8") (pinfunction "DQ6_D8") (pintype "bidirectional"))
    )
    (net (code "77") (name "/SDRAM_DQ7") (class "Default")
      (node (ref "U25") (pin "E9") (pinfunction "DQ7_E9") (pintype "bidirectional"))
    )
    (net (code "78") (name "/SDRAM_DQ8") (class "Default")
      (node (ref "U25") (pin "E1") (pinfunction "DQ8_E1") (pintype "bidirectional"))
    )
    (net (code "79") (name "/SDRAM_DQ9") (class "Default")
      (node (ref "U25") (pin "D2") (pinfunction "DQ9_D2") (pintype "bidirectional"))
    )
    (net (code "80") (name "/SDRAM_DQ10") (class "Default")
      (node (ref "U25") (pin "D1") (pinfunction "DQ10_D1") (pintype "bidirectional"))
    )
    (net (code "81") (name "/SDRAM_DQ11") (class "Default")
      (node (ref "U25") (pin "C2") (pinfunction "DQ11_C2") (pintype "bidirectional"))
    )
    (net (code "82") (name "/SDRAM_DQ12") (class "Default")
      (node (ref "U25") (pin "C1") (pinfunction "DQ12_C1") (pintype "bidirectional"))
    )
    (net (code "83") (name "/SDRAM_DQ13") (class "Default")
      (node (ref "U25") (pin "B2") (pinfunction "DQ13_B2") (pintype "bidirectional"))
    )
    (net (code "84") (name "/SDRAM_DQ14") (class "Default")
      (node (ref "U25") (pin "B1") (pinfunction "DQ14_B1") (pintype "bidirectional"))
    )
    (net (code "85") (name "/SDRAM_DQ15") (class "Default")
      (node (ref "U25") (pin "A2") (pinfunction "DQ15_A2") (pintype "bidirectional"))
    )
    (net (code "86") (name "/SDRAM_DQM0") (class "Default")
      (node (ref "U25") (pin "E8") (pinfunction "LDQM_E8") (pintype "input"))
    )
    (net (code "87") (name "/SDRAM_DQM1") (class "Default")
      (node (ref "U25") (pin "F1") (pinfunction "UDQM_F1") (pintype "input"))
    )
    (net (code "88") (name "/SDRAM_PWR_EN") (class "Default")
      (node (ref "R24") (pin "1") (pinfunction "1_1") (pintype "passive"))
      (node (ref "U5") (pin "12") (pinfunction "EN_12") (pintype "passive"))
    )
    (net (code "89") (name "/SDRAM_PWR_GOOD") (class "Default")
      (node (ref "U5") (pin "7") (pinfunction "PG_7") (pintype "passive"))
    )
    (net (code "90") (name "/SDRAM_RAS#") (class "Default")
      (node (ref "U25") (pin "F8") (pinfunction "~{RAS}_F8") (pintype "input"))
    )
    (net (code "91") (name "/SDRAM_SDCLK") (class "Default")
      (node (ref "U25") (pin "F2") (pinfunction "CLK_F2") (pintype "input"))
    )
    (net (code "92") (name "/SDRAM_SDCS#") (class "Default")
      (node (ref "U25") (pin "G9") (pinfunction "~{CS}_G9") (pintype "input"))
    )
    (net (code "93") (name "/SDRAM_WE#") (class "Default")
      (node (ref "U25") (pin "F9") (pinfunction "~{WE}_F9") (pintype "input"))
    )
    (net (code "94") (name "/SPI1_CLK") (class "Default")
      (node (ref "X6") (pin "47") (pinfunction "24_47") (pintype "passive"))
    )
    (net (code "95") (name "/SPI1_MISO") (class "Default")
      (node (ref "X6") (pin "41") (pinfunction "21_41") (pintype "passive"))
    )
    (net (code "96") (name "/SPI1_MOSI") (class "Default")
      (node (ref "X6") (pin "43") (pinfunction "22_43") (pintype "passive"))
    )
    (net (code "97") (name "/SPI1_SS2") (class "Default")
      (node (ref "X6") (pin "44") (pinfunction "23_44") (pintype "passive"))
    )
    (net (code "98") (name "/TOUCH_IRQ") (class "Default")
      (node (ref "X6") (pin "36") (pinfunction "19_36") (pintype "passive"))
    )
    (net (code "99") (name "/TOUCH_RST") (class "Default")
      (node (ref "X6") (pin "37") (pinfunction "19_37") (pintype "passive"))
    )
    (net (code "100") (name "/USBHS_N") (class "Default")
      (node (ref "U26") (pin "1") (pinfunction "1_1") (pintype "passive"))
      (node (ref "X3") (pin "2") (pinfunction "D-_2") (pintype "bidirectional"))
    )
    (net (code "101") (name "/USBHS_P") (class "Default")
      (node (ref "U26") (pin "2") (pinfunction "2_2") (pintype "passive"))
      (node (ref "X3") (pin "3") (pinfunction "D+_3") (pintype "bidirectional"))
    )
    (net (code "102") (name "GND") (class "Default")
      (node (ref "C109") (pin "2") (pinfunction "2_2") (pintype "passive"))
      (node (ref "C110") (pin "1") (pinfunction "1_1") (pintype "passive"))
      (node (ref "C111") (pin "2") (pinfunction "2_2") (pintype "passive"))
      (node (ref "C112") (pin "2") (pinfunction "2_2") (pintype "passive"))
      (node (ref "C113") (pin "2") (pinfunction "2_2") (pintype "passive"))
      (node (ref "C114") (pin "2") (pinfunction "2_2") (pintype "passive"))
      (node (ref "C115") (pin "2") (pinfunction "2_2") (pintype "passive"))
      (node (ref "C116") (pin "2") (pinfunction "2_2") (pintype "passive"))
      (node (ref "C117") (pin "2") (pinfunction "2_2") (pintype "passive"))
      (node (ref "C118") (pin "1") (pinfunction "1_1") (pintype "passive"))
      (node (ref "C119") (pin "2") (pinfunction "2_2") (pintype "passive"))
      (node (ref "C120") (pin "2") (pinfunction "2_2") (pintype "passive"))
      (node (ref "C121") (pin "2") (pinfunction "2_2") (pintype "passive"))
      (node (ref "C122") (pin "2") (pinfunction "2_2") (pintype "passive"))
      (node (ref "C123") (pin "1") (pinfunction "1_1") (pintype "passive"))
      (node (ref "C34") (pin "1") (pinfunction "1_1") (pintype "passive"))
      (node (ref "C35") (pin "2") (pinfunction "2_2") (pintype "passive"))
      (node (ref "C36") (pin "2") (pinfunction "2_2") (pintype "passive"))
      (node (ref "C37") (pin "2") (pinfunction "2_2") (pintype "passive"))
      (node (ref "C38") (pin "2") (pinfunction "2_2") (pintype "passive"))
      (node (ref "C41") (pin "2") (pinfunction "2_2") (pintype "passive"))
      (node (ref "C42") (pin "2") (pinfunction "2_2") (pintype "passive"))
      (node (ref "C43") (pin "2") (pinfunction "2_2") (pintype "passive"))
      (node (ref "C44") (pin "2") (pinfunction "2_2") (pintype "passive"))
      (node (ref "C45") (pin "2") (pinfunction "2_2") (pintype "passive"))
      (node (ref "C46") (pin "2") (pinfunction "2_2") (pintype "passive"))
      (node (ref "C47") (pin "2") (pinfunction "2_2") (pintype "passive"))
      (node (ref "C48") (pin "1") (pinfunction "1_1") (pintype "passive"))
      (node (ref "C49") (pin "2") (pinfunction "2_2") (pintype "passive"))
      (node (ref "C50") (pin "1") (pinfunction "1_1") (pintype "passive"))
      (node (ref "M1") (pin "2") (pinfunction "GND_2") (pintype "passive"))
      (node (ref "M2") (pin "2") (pinfunction "LR_2") (pintype "passive"))
      (node (ref "M2") (pin "3") (pinfunction "GND_3") (pintype "passive"))
      (node (ref "M3") (pin "4") (pinfunction "GND_4") (pintype "passive"))
      (node (ref "M4") (pin "4") (pinfunction "GND_4") (pintype "passive"))
      (node (ref "R24") (pin "2") (pinfunction "2_2") (pintype "passive"))
      (node (ref "R25") (pin "1") (pinfunction "1_1") (pintype "passive"))
      (node (ref "U24") (pin "10") (pinfunction "GND_10") (pintype "power_in"))
      (node (ref "U24") (pin "PAD") (pinfunction "PAD_PAD") (pintype "passive"))
      (node (ref "U25") (pin "A1") (pinfunction "VSS_A1") (pintype "power_in"))
      (node (ref "U25") (pin "A3") (pinfunction "VSSQ_A3") (pintype "power_in"))
      (node (ref "U25") (pin "B7") (pinfunction "VSSQ_B7") (pintype "power_in"))
      (node (ref "U25") (pin "C3") (pinfunction "VSSQ_C3") (pintype "power_in"))
      (node (ref "U25") (pin "D7") (pinfunction "VSSQ_D7") (pintype "power_in"))
      (node (ref "U25") (pin "E3") (pinfunction "VSS_E3") (pintype "power_in"))
      (node (ref "U25") (pin "J1") (pinfunction "VSS_J1") (pintype "power_in"))
      (node (ref "U26") (pin "7") (pinfunction "7_7") (pintype "passive"))
      (node (ref "U27") (pin "2") (pinfunction "GND_2") (pintype "power_in"))
      (node (ref "U27") (pin "5") (pinfunction "EP_5") (pintype "power_in"))
      (node (ref "U5") (pin "13") (pinfunction "EP_13") (pintype "passive"))
      (node (ref "U5") (pin "3") (pinfunction "GND_3") (pintype "passive"))
      (node (ref "U6") (pin "A6") (pinfunction "VSS_A6") (pintype "power_in"))
      (node (ref "U6") (pin "C4") (pinfunction "VSSQ_C4") (pintype "power_in"))
      (node (ref "U6") (pin "E7") (pinfunction "VSS_E7") (pintype "power_in"))
      (node (ref "U6") (pin "G5") (pinfunction "VSS_G5") (pintype "power_in"))
      (node (ref "U6") (pin "H10") (pinfunction "VSS_H10") (pintype "power_in"))
      (node (ref "U6") (pin "K8") (pinfunction "VSS_K8") (pintype "power_in"))
      (node (ref "U6") (pin "N2") (pinfunction "VSSQ_N2") (pintype "power_in"))
      (node (ref "U6") (pin "N5") (pinfunction "VSSQ_N5") (pintype "power_in"))
      (node (ref "U6") (pin "P4") (pinfunction "VSSQ_P4") (pintype "power_in"))
      (node (ref "U6") (pin "P6") (pinfunction "VSSQ_P6") (pintype "power_in"))
      (node (ref "U7") (pin "4") (pinfunction "IN-_4") (pintype "input"))
      (node (ref "U7") (pin "5") (pinfunction "GND_5") (pintype "power_in"))
      (node (ref "U8") (pin "4") (pinfunction "GND_4") (pintype "passive"))
      (node (ref "U8") (pin "8") (pinfunction "L_8") (pintype "passive"))
      (node (ref "U9") (pin "2") (pinfunction "GND_2") (pintype "power_in"))
      (node (ref "X3") (pin "5") (pinfunction "GND_5") (pintype "power_in"))
      (node (ref "X3") (pin "G1") (pinfunction "CASE_G1") (pintype "power_in"))
      (node (ref "X6") (pin "1") (pinfunction "1_1") (pintype "passive"))
      (node (ref "X6") (pin "16") (pinfunction "9_16") (pintype "passive"))
      (node (ref "X6") (pin "17") (pinfunction "9_17") (pintype "passive"))
      (node (ref "X6") (pin "2") (pinfunction "2_2") (pintype "passive"))
      (node (ref "X6") (pin "23") (pinfunction "12_23") (pintype "passive"))
      (node (ref "X6") (pin "24") (pinfunction "13_24") (pintype "passive"))
      (node (ref "X6") (pin "27") (pinfunction "14_27") (pintype "passive"))
      (node (ref "X6") (pin "30") (pinfunction "16_30") (pintype "passive"))
      (node (ref "X6") (pin "31") (pinfunction "16_31") (pintype "passive"))
      (node (ref "X6") (pin "34") (pinfunction "18_34") (pintype "passive"))
      (node (ref "X6") (pin "39") (pinfunction "20_39") (pintype "passive"))
      (node (ref "X6") (pin "42") (pinfunction "22_42") (pintype "passive"))
      (node (ref "X6") (pin "45") (pinfunction "23_45") (pintype "passive"))
      (node (ref "X6") (pin "46") (pinfunction "24_46") (pintype "passive"))
      (node (ref "X6") (pin "48") (pinfunction "25_48") (pintype "passive"))
      (node (ref "X6") (pin "53") (pinfunction "27_53") (pintype "passive"))
      (node (ref "X6") (pin "54") (pinfunction "28_54") (pintype "passive"))
      (node (ref "X6") (pin "8") (pinfunction "5_8") (pintype "passive"))
      (node (ref "X6") (pin "9") (pinfunction "5_9") (pintype "passive"))
    )
    (net (code "103") (name "Net-(M3-Out-)") (class "Default")
      (node (ref "M3") (pin "2") (pinfunction "Out-_2") (pintype "passive"))
      (node (ref "U9") (pin "1") (pinfunction "IN+_1") (pintype "passive"))
    )
    (net (code "104") (name "Net-(M3-VDD)") (class "Default")
      (node (ref "C121") (pin "1") (pinfunction "1_1") (pintype "passive"))
      (node (ref "C122") (pin "1") (pinfunction "1_1") (pintype "passive"))
      (node (ref "M3") (pin "1") (pinfunction "VDD_1") (pintype "passive"))
      (node (ref "U27") (pin "1") (pinfunction "OUT_1") (pintype "power_in"))
      (node (ref "U7") (pin "1") (pinfunction "REF_1") (pintype "input"))
      (node (ref "U9") (pin "5") (pinfunction "VCC_5") (pintype "power_in"))
    )
    (net (code "105") (name "Net-(U5-CTRL)") (class "Default")
      (node (ref "C110") (pin "2") (pinfunction "2_2") (pintype "passive"))
      (node (ref "L8") (pin "1") (pinfunction "1_1") (pintype "passive"))
      (node (ref "U5") (pin "4") (pinfunction "CTRL_4") (pintype "passive"))
      (node (ref "U5") (pin "5") (pinfunction "VOUT_5") (pintype "passive"))
    )
    (net (code "106") (name "Net-(U5-SW)") (class "Default")
      (node (ref "L8") (pin "2") (pinfunction "2_2") (pintype "passive"))
      (node (ref "U5") (pin "2") (pinfunction "SW_2") (pintype "passive"))
    )
    (net (code "107") (name "Net-(U6-VDDI)") (class "Default")
      (node (ref "C111") (pin "1") (pinfunction "1_1") (pintype "passive"))
      (node (ref "C112") (pin "1") (pinfunction "1_1") (pintype "passive"))
      (node (ref "U6") (pin "C2") (pinfunction "VDDI_C2") (pintype "power_in"))
    )
    (net (code "108") (name "Net-(U7-IN+)") (class "Default")
      (node (ref "C50") (pin "2") (pinfunction "2_2") (pintype "passive"))
      (node (ref "R27") (pin "2") (pinfunction "2_2") (pintype "passive"))
      (node (ref "U7") (pin "3") (pinfunction "IN+_3") (pintype "input"))
    )
    (net (code "109") (name "Net-(U8-W)") (class "Default")
      (node (ref "C39") (pin "2") (pinfunction "2_2") (pintype "passive"))
      (node (ref "U8") (pin "6") (pinfunction "W_6") (pintype "passive"))
    )
    (net (code "110") (name "Net-(U9-IN-)") (class "Default")
      (node (ref "C39") (pin "1") (pinfunction "1_1") (pintype "passive"))
      (node (ref "C40") (pin "1") (pinfunction "1_1") (pintype "passive"))
      (node (ref "R25") (pin "2") (pinfunction "2_2") (pintype "passive"))
      (node (ref "R26") (pin "1") (pinfunction "1_1") (pintype "passive"))
      (node (ref "U9") (pin "3") (pinfunction "IN-_3") (pintype "passive"))
    )
    (net (code "111") (name "Net-(U9-OUT)") (class "Default")
      (node (ref "C40") (pin "2") (pinfunction "2_2") (pintype "passive"))
      (node (ref "R26") (pin "2") (pinfunction "2_2") (pintype "passive"))
      (node (ref "R27") (pin "1") (pinfunction "1_1") (pintype "passive"))
      (node (ref "U9") (pin "4") (pinfunction "OUT_4") (pintype "passive"))
    )
    (net (code "112") (name "Net-(U24-1B3)") (class "Default")
      (node (ref "R53") (pin "5") (pinfunction "5_5") (pintype "passive"))
      (node (ref "U24") (pin "14") (pinfunction "1B3_14") (pintype "bidirectional"))
      (node (ref "U6") (pin "A5") (pinfunction "DAT2_A5") (pintype "bidirectional"))
    )
    (net (code "113") (name "Net-(U24-1B4)") (class "Default")
      (node (ref "R53") (pin "6") (pinfunction "6_6") (pintype "passive"))
      (node (ref "U24") (pin "12") (pinfunction "1B4_12") (pintype "bidirectional"))
      (node (ref "U6") (pin "A4") (pinfunction "DAT1_A4") (pintype "bidirectional"))
    )
    (net (code "114") (name "Net-(U24-2B1)") (class "Default")
      (node (ref "R52") (pin "5") (pinfunction "5_5") (pintype "passive"))
      (node (ref "U24") (pin "9") (pinfunction "2B1_9") (pintype "bidirectional"))
      (node (ref "U6") (pin "B2") (pinfunction "DAT3_B2") (pintype "bidirectional"))
    )
    (net (code "115") (name "Net-(U24-2B2)") (class "Default")
      (node (ref "R52") (pin "6") (pinfunction "6_6") (pintype "passive"))
      (node (ref "U24") (pin "7") (pinfunction "2B2_7") (pintype "bidirectional"))
      (node (ref "U6") (pin "M5") (pinfunction "CMD_M5") (pintype "bidirectional"))
    )
    (net (code "116") (name "Net-(U24-2B3)") (class "Default")
      (node (ref "R52") (pin "7") (pinfunction "7_7") (pintype "passive"))
      (node (ref "U24") (pin "5") (pinfunction "2B3_5") (pintype "bidirectional"))
      (node (ref "U6") (pin "M6") (pinfunction "CLK_M6") (pintype "input"))
    )
    (net (code "117") (name "Net-(U24-2B4)") (class "Default")
      (node (ref "R52") (pin "8") (pinfunction "8_8") (pintype "passive"))
      (node (ref "U24") (pin "3") (pinfunction "2B4_3") (pintype "bidirectional"))
      (node (ref "U6") (pin "A3") (pinfunction "DAT0_A3") (pintype "bidirectional"))
    )
    (net (code "118") (name "Net-(X3-ID)") (class "Default")
      (node (ref "U26") (pin "3") (pinfunction "3_3") (pintype "passive"))
      (node (ref "X3") (pin "4") (pinfunction "ID_4") (pintype "passive"))
    )
    (net (code "119") (name "Net-(X3-VBUS)") (class "Default")
      (node (ref "C123") (pin "2") (pinfunction "2_2") (pintype "passive"))
      (node (ref "L18") (pin "1") (pinfunction "1_1") (pintype "passive"))
      (node (ref "U26") (pin "6") (pinfunction "6_6") (pintype "passive"))
      (node (ref "X3") (pin "1") (pinfunction "VBUS_1") (pintype "power_in"))
    )
    (net (code "120") (name "SYS_V") (class "Default")
      (node (ref "C34") (pin "2") (pinfunction "2_2") (pintype "passive"))
      (node (ref "U5") (pin "1") (pinfunction "VIN_1") (pintype "passive"))
      (node (ref "U5") (pin "10") (pinfunction "VSEL2_10") (pintype "passive"))
      (node (ref "U5") (pin "11") (pinfunction "VSEL1_11") (pintype "passive"))
      (node (ref "U5") (pin "8") (pinfunction "VSEL4_8") (pintype "passive"))
      (node (ref "U5") (pin "9") (pinfunction "VSEL3_9") (pintype "passive"))
      (node (ref "X6") (pin "57") (pinfunction "29_57") (pintype "passive"))
      (node (ref "X6") (pin "58") (pinfunction "30_58") (pintype "passive"))
      (node (ref "X6") (pin "59") (pinfunction "30_59") (pintype "passive"))
      (node (ref "X6") (pin "60") (pinfunction "31_60") (pintype "passive"))
    )
    (net (code "121") (name "VBUSH") (class "Default")
      (node (ref "L18") (pin "2") (pinfunction "2_2") (pintype "passive"))
    )
    (net (code "122") (name "unconnected-(M3-Out+-Pad3)") (class "Default")
      (node (ref "M3") (pin "3") (pinfunction "Out+_3") (pintype "passive"))
    )
    (net (code "123") (name "unconnected-(M4-Out--Pad2)") (class "Default")
      (node (ref "M4") (pin "2") (pinfunction "Out-_2") (pintype "passive"))
    )
    (net (code "124") (name "unconnected-(R53-Pad7)") (class "Default")
      (node (ref "R53") (pin "7") (pinfunction "7_7") (pintype "passive"))
    )
    (net (code "125") (name "unconnected-(R53-Pad8)") (class "Default")
      (node (ref "R53") (pin "8") (pinfunction "8_8") (pintype "passive"))
    )
    (net (code "126") (name "unconnected-(U6-DAT4-PadB3)") (class "Default")
      (node (ref "U6") (pin "B3") (pinfunction "DAT4_B3") (pintype "bidirectional"))
    )
    (net (code "127") (name "unconnected-(U6-DAT5-PadB4)") (class "Default")
      (node (ref "U6") (pin "B4") (pinfunction "DAT5_B4") (pintype "bidirectional"))
    )
    (net (code "128") (name "unconnected-(U6-DAT6-PadB5)") (class "Default")
      (node (ref "U6") (pin "B5") (pinfunction "DAT6_B5") (pintype "bidirectional"))
    )
    (net (code "129") (name "unconnected-(U6-DAT7-PadB6)") (class "Default")
      (node (ref "U6") (pin "B6") (pinfunction "DAT7_B6") (pintype "bidirectional"))
    )
    (net (code "130") (name "unconnected-(U6-DS-PadH5)") (class "Default")
      (node (ref "U6") (pin "H5") (pinfunction "DS_H5") (pintype "output"))
    )
    (net (code "131") (name "unconnected-(U8-H-Pad1)") (class "Default")
      (node (ref "U8") (pin "1") (pinfunction "H_1") (pintype "passive"))
    )
    (net (code "132") (name "unconnected-(U24-1A1-Pad2)") (class "Default")
      (node (ref "U24") (pin "2") (pinfunction "1A1_2") (pintype "bidirectional"))
    )
    (net (code "133") (name "unconnected-(U24-1A2-Pad4)") (class "Default")
      (node (ref "U24") (pin "4") (pinfunction "1A2_4") (pintype "bidirectional"))
    )
    (net (code "134") (name "unconnected-(U24-1B1-Pad18)") (class "Default")
      (node (ref "U24") (pin "18") (pinfunction "1B1_18") (pintype "bidirectional"))
    )
    (net (code "135") (name "unconnected-(U24-1B2-Pad16)") (class "Default")
      (node (ref "U24") (pin "16") (pinfunction "1B2_16") (pintype "bidirectional"))
    )
    (net (code "136") (name "unconnected-(U25-NC-PadE2)") (class "Default")
      (node (ref "U25") (pin "E2") (pinfunction "NC_E2") (pintype "passive"))
    )
  )
)
